# working.net
KiCad netlist of a schematic drawn in EAGLE
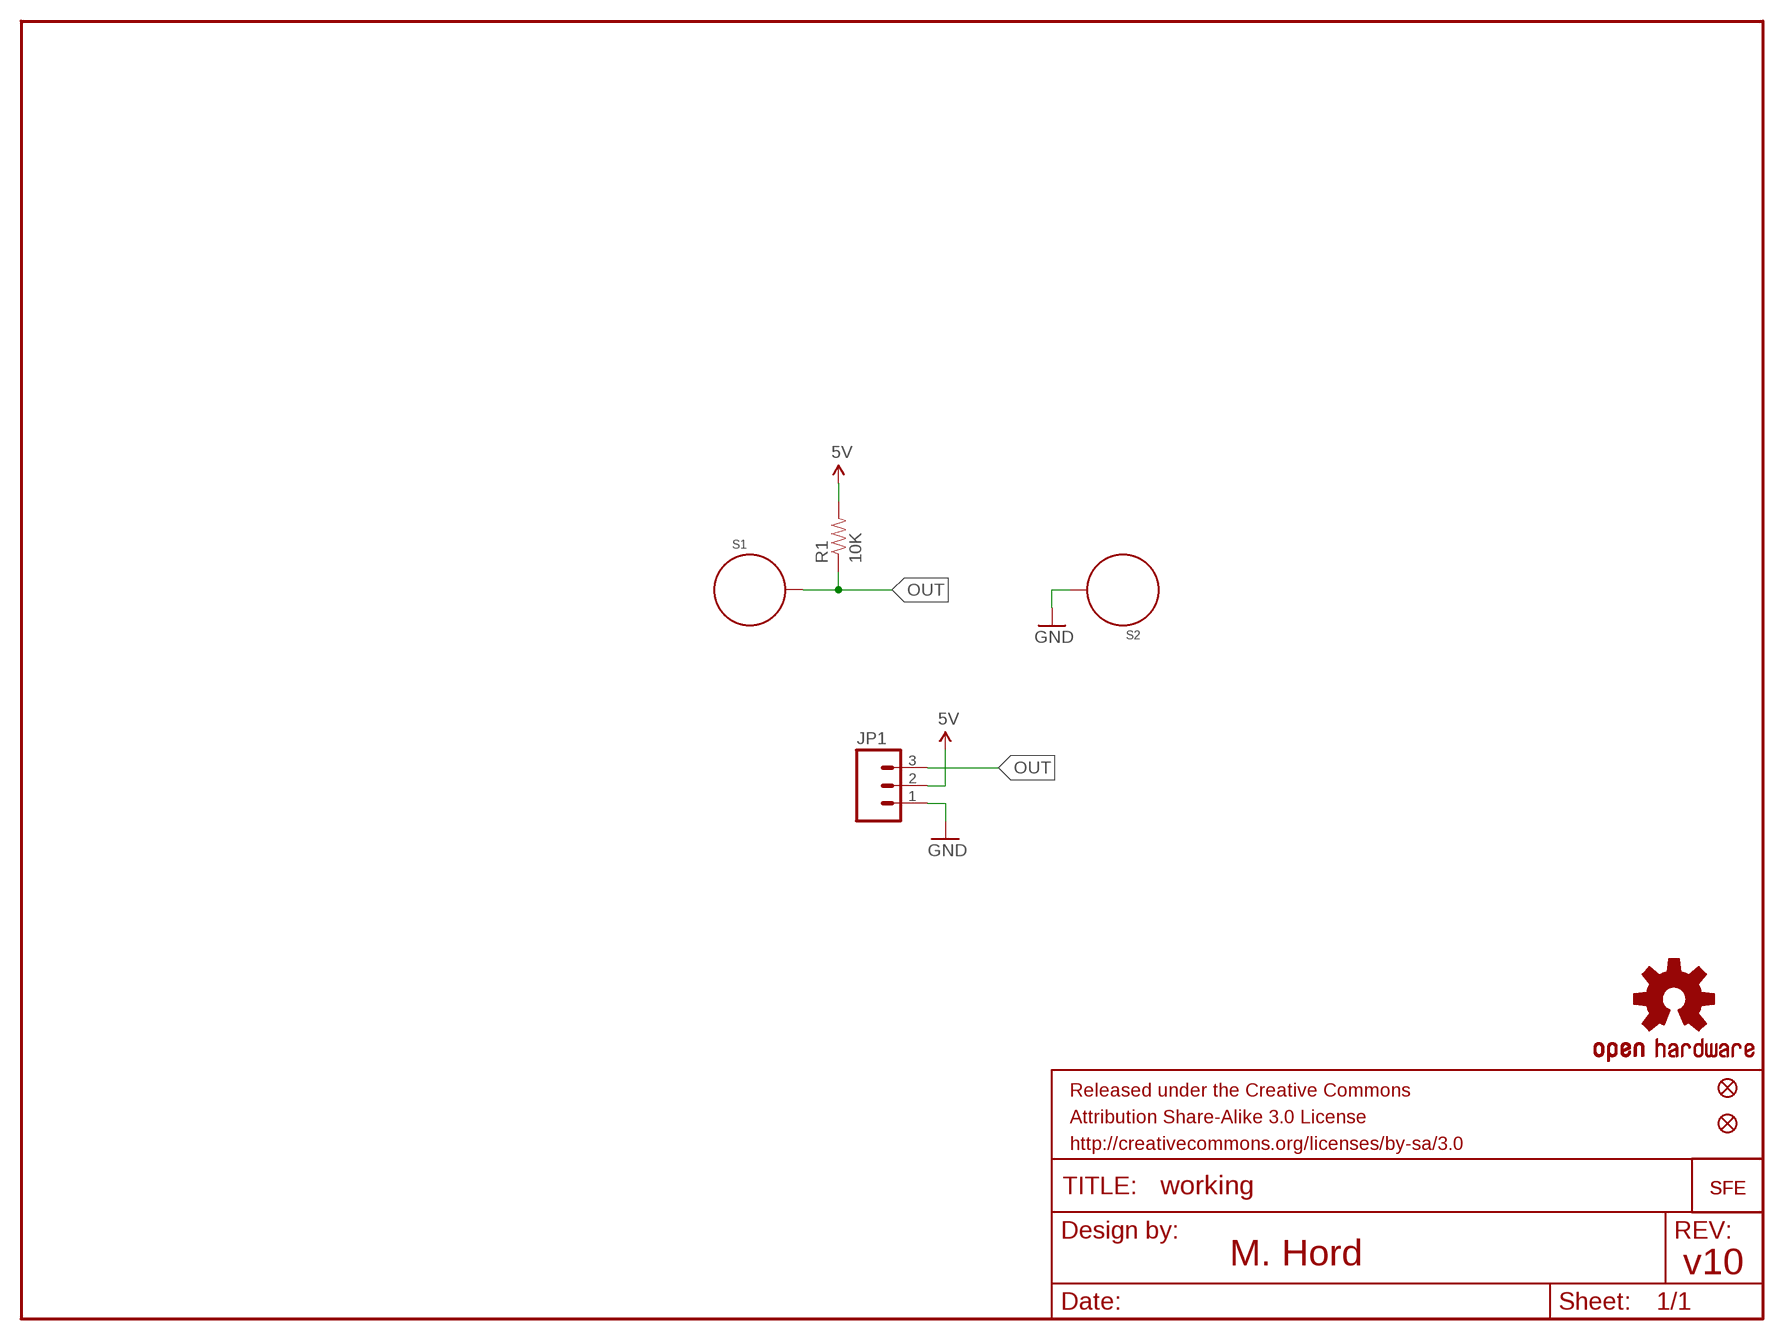
[diagram p0: schematic, sheet 1]

(export (version "E")
  (design (tool "Eeschema 10.0.6"))
  (components
    (comp (ref "FID1")
      (value "FIDUCIALUFIDUCIAL")
      (footprint "eagle-import:MICRO-FIDUCIAL")
      (libsource (lib "eagle-import") (part "FIDUCIALUFIDUCIAL"))
    )
    (comp (ref "FID2")
      (value "FIDUCIALUFIDUCIAL")
      (footprint "eagle-import:MICRO-FIDUCIAL")
      (libsource (lib "eagle-import") (part "FIDUCIALUFIDUCIAL"))
    )
    (comp (ref "FRAME1")
      (value "FRAME-LETTER")
      (footprint "eagle-import:CREATIVE_COMMONS")
      (libsource (lib "eagle-import") (part "FRAME-LETTER"))
    )
    (comp (ref "JP1")
      (value "M03SMD_RA_MALE")
      (footprint "eagle-import:1X03_SMD_RA_MALE")
      (libsource (lib "eagle-import") (part "M03SMD_RA_MALE"))
    )
    (comp (ref "LOGO1")
      (value "OSHW-LOGOS")
      (footprint "eagle-import:OSHW-LOGO-S")
      (libsource (lib "eagle-import") (part "OSHW-LOGOS"))
    )
    (comp (ref "LOGO2")
      (value "LOGO-SFESK")
      (footprint "eagle-import:SFE-LOGO-FLAME")
      (libsource (lib "eagle-import") (part "LOGO-SFESK"))
    )
    (comp (ref "LOGO3")
      (value "OSHW-LOGOS")
      (footprint "eagle-import:OSHW-LOGO-S")
      (libsource (lib "eagle-import") (part "OSHW-LOGOS"))
    )
    (comp (ref "LOGO4")
      (value "LOGO-SFESK")
      (footprint "eagle-import:SFE-LOGO-FLAME")
      (libsource (lib "eagle-import") (part "LOGO-SFESK"))
    )
    (comp (ref "R1")
      (value "10K")
      (footprint "eagle-import:0603-RES")
      (libsource (lib "eagle-import") (part "10KOHM1/10W1%(0603)0603"))
    )
    (comp (ref "S1")
      (value "STANDOFF_ELECTRICAL")
      (footprint "eagle-import:STANDOFF-ELECTRICAL")
      (libsource (lib "eagle-import") (part "STANDOFF_ELECTRICAL"))
    )
    (comp (ref "S2")
      (value "STANDOFF_ELECTRICAL")
      (footprint "eagle-import:STANDOFF-ELECTRICAL")
      (libsource (lib "eagle-import") (part "STANDOFF_ELECTRICAL"))
    )
  )
  (nets
    (net (code "1") (name "5V") (class "Default")
      (node (ref "JP1") (pin "2") (pinfunction "2_2") (pintype "passive"))
      (node (ref "R1") (pin "2") (pinfunction "2_2") (pintype "passive"))
    )
    (net (code "2") (name "GND") (class "Default")
      (node (ref "JP1") (pin "1") (pinfunction "1_1") (pintype "passive"))
      (node (ref "S2") (pin "P1") (pinfunction "P$1_P1") (pintype "bidirectional"))
    )
    (net (code "3") (name "OUT") (class "Default")
      (node (ref "JP1") (pin "3") (pinfunction "3_3") (pintype "passive"))
      (node (ref "R1") (pin "1") (pinfunction "1_1") (pintype "passive"))
      (node (ref "S1") (pin "P1") (pinfunction "P$1_P1") (pintype "bidirectional"))
    )
  )
)
